# Dash.net
KiCad netlist of a schematic drawn in EAGLE
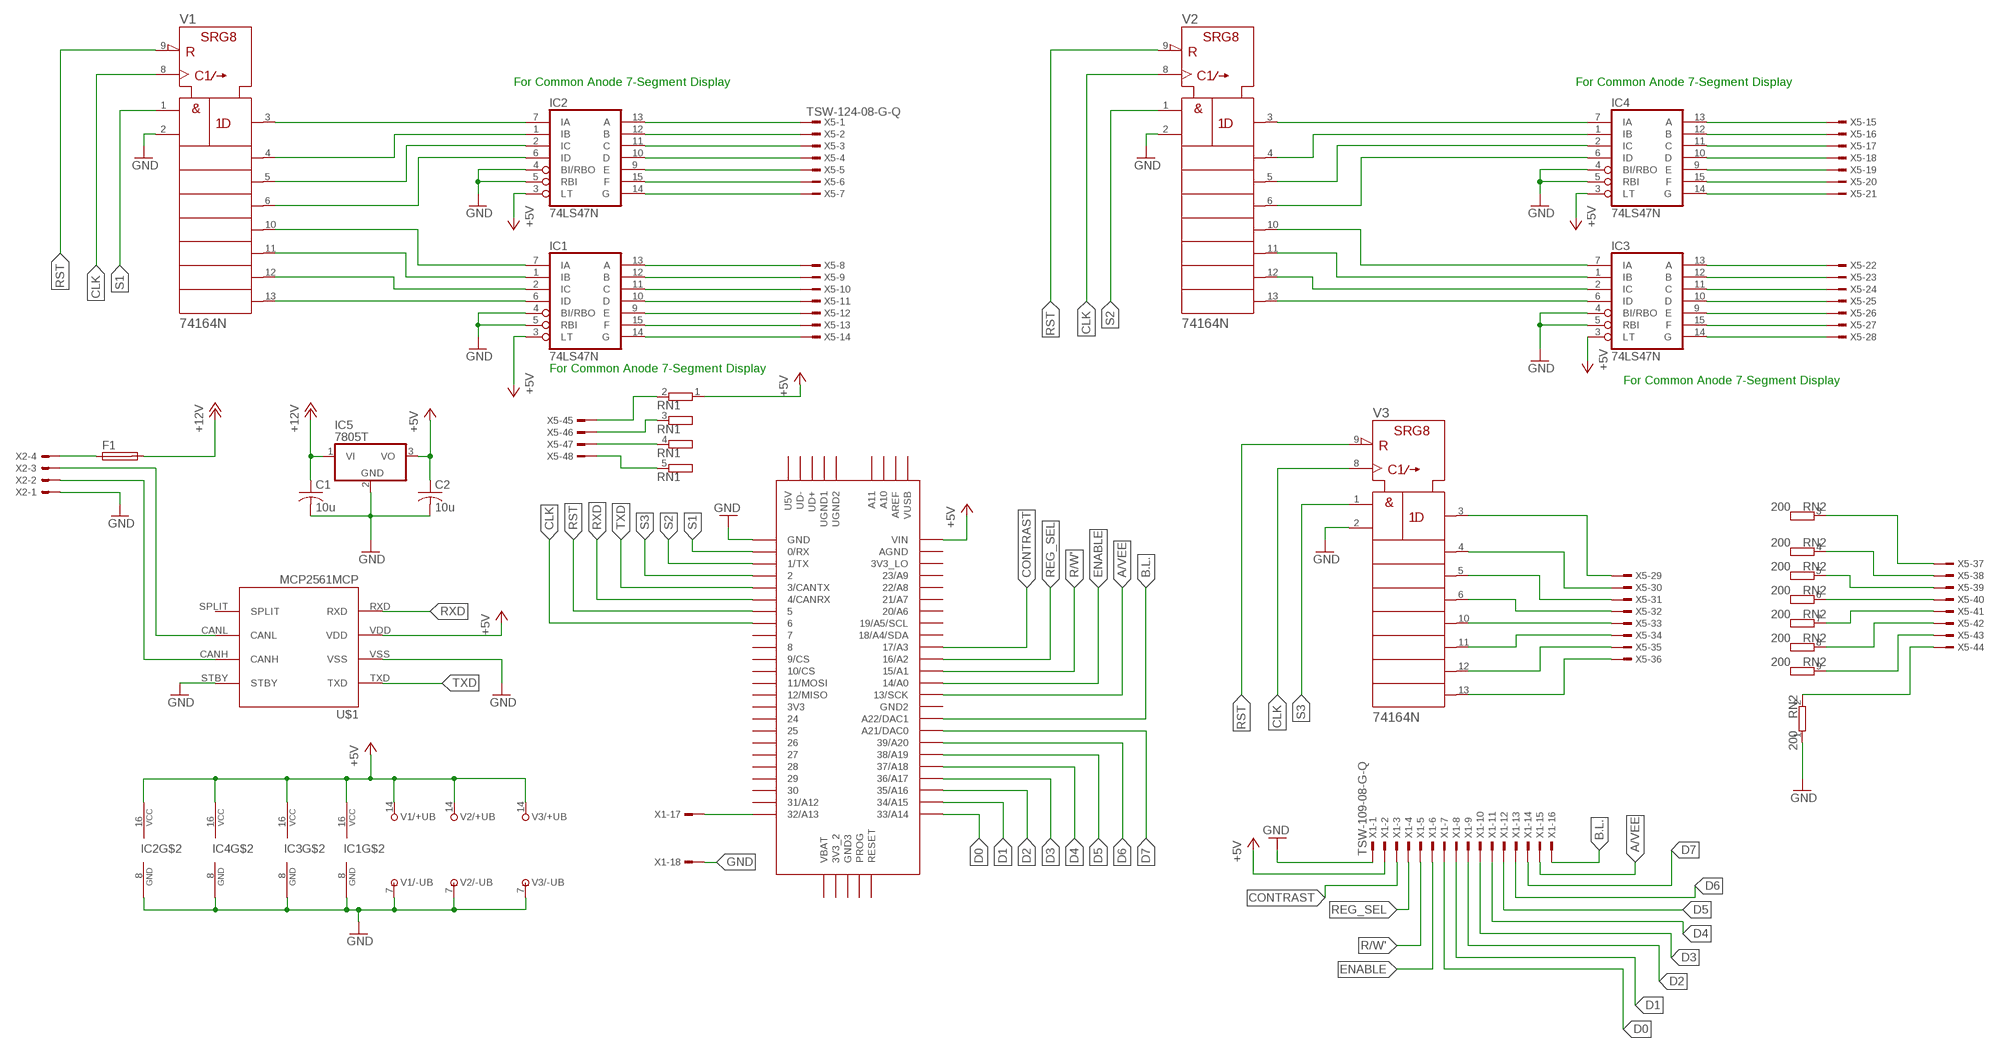
[diagram p0: schematic, sheet 1]

(export (version "E")
  (design (tool "Eeschema 10.0.6"))
  (components
    (comp (ref "C1")
      (value "10u")
      (footprint "eagle-import:C050-024X044")
      (libsource (lib "eagle-import") (part "C-US050-024X044"))
    )
    (comp (ref "C2")
      (value "10u")
      (footprint "eagle-import:C050-024X044")
      (fields (field (name "CAPACITANCE") "10uF"))
      (libsource (lib "eagle-import") (part "C-US050-024X044"))
    )
    (comp (ref "F1")
      (value "FUSEBLANK_5X20MM")
      (footprint "eagle-import:FUSE_HOLDER_5X20MM")
      (libsource (lib "eagle-import") (part "FUSEBLANK_5X20MM"))
    )
    (comp (ref "IC1")
      (value "74LS47N")
      (footprint "eagle-import:DIL16")
      (libsource (lib "eagle-import") (part "7447NLS"))
    )
    (comp (ref "IC2")
      (value "74LS47N")
      (footprint "eagle-import:DIL16")
      (libsource (lib "eagle-import") (part "7447NLS"))
    )
    (comp (ref "IC3")
      (value "74LS47N")
      (footprint "eagle-import:DIL16")
      (libsource (lib "eagle-import") (part "7447NLS"))
    )
    (comp (ref "IC4")
      (value "74LS47N")
      (footprint "eagle-import:DIL16")
      (libsource (lib "eagle-import") (part "7447NLS"))
    )
    (comp (ref "IC5")
      (value "7805T")
      (footprint "eagle-import:TO220H")
      (libsource (lib "eagle-import") (part "78T05"))
    )
    (comp (ref "RN1")
      (value "GE04RP")
      (footprint "eagle-import:SIL5")
      (libsource (lib "eagle-import") (part "GE04RP"))
    )
    (comp (ref "RN2")
      (value "200")
      (footprint "eagle-import:SIL9")
      (libsource (lib "eagle-import") (part "GE08RP"))
    )
    (comp (ref "U$1")
      (value "MCP2561MCP")
      (footprint "eagle-import:MCP2561_PDIP")
      (libsource (lib "eagle-import") (part "MCP2561MCP"))
    )
    (comp (ref "U$2")
      (value "TEENSY_3.5/3.6")
      (footprint "eagle-import:TEENSY_3.5_3.6")
      (libsource (lib "eagle-import") (part "TEENSY_3.5/3.6"))
    )
    (comp (ref "V1")
      (value "74164N")
      (footprint "eagle-import:DIL14")
      (libsource (lib "eagle-import") (part "74164N"))
    )
    (comp (ref "V2")
      (value "74164N")
      (footprint "eagle-import:DIL14")
      (libsource (lib "eagle-import") (part "74164N"))
    )
    (comp (ref "V3")
      (value "74164N")
      (footprint "eagle-import:DIL14")
      (libsource (lib "eagle-import") (part "74164N"))
    )
    (comp (ref "X1")
      (value "TSW-109-08-G-Q")
      (footprint "eagle-import:TSW-109-XX-G-Q")
      (fields (field (name "MF") "Samtec Inc.") (field (name "MPN") "TSW-109-07-G-Q"))
      (libsource (lib "eagle-import") (part "TSW-109--G-Q08"))
    )
    (comp (ref "X2")
      (value "KK-156-4")
      (footprint "eagle-import:KK-156-4")
      (fields (field (name "MF") "MOLEX"))
      (libsource (lib "eagle-import") (part "KK-156-4"))
    )
    (comp (ref "X5")
      (value "TSW-124-08-G-Q")
      (footprint "eagle-import:TSW-124-XX-G-Q")
      (fields (field (name "MF") "Samtec Inc.") (field (name "MPN") "TSW-124-07-G-Q"))
      (libsource (lib "eagle-import") (part "TSW-124--G-Q08"))
    )
  )
  (nets
    (net (code "1") (name "+5V") (class "Default")
      (node (ref "C2") (pin "1") (pinfunction "1_1") (pintype "passive"))
      (node (ref "IC1") (pin "16") (pinfunction "VCC_16") (pintype "power_in"))
      (node (ref "IC1") (pin "3") (pinfunction "LT_3") (pintype "input"))
      (node (ref "IC2") (pin "16") (pinfunction "VCC_16") (pintype "power_in"))
      (node (ref "IC2") (pin "3") (pinfunction "LT_3") (pintype "input"))
      (node (ref "IC3") (pin "16") (pinfunction "VCC_16") (pintype "power_in"))
      (node (ref "IC3") (pin "3") (pinfunction "LT_3") (pintype "input"))
      (node (ref "IC4") (pin "16") (pinfunction "VCC_16") (pintype "power_in"))
      (node (ref "IC4") (pin "3") (pinfunction "LT_3") (pintype "input"))
      (node (ref "IC5") (pin "3") (pinfunction "VO_3") (pintype "passive"))
      (node (ref "RN1") (pin "1") (pinfunction "1_1") (pintype "passive"))
      (node (ref "U$1") (pin "VDD") (pinfunction "VDD_VDD") (pintype "bidirectional"))
      (node (ref "U$2") (pin "VIN") (pinfunction "VIN_VIN") (pintype "bidirectional"))
      (node (ref "V1") (pin "14") (pinfunction "+UB_14") (pintype "power_in"))
      (node (ref "V2") (pin "14") (pinfunction "+UB_14") (pintype "power_in"))
      (node (ref "V3") (pin "14") (pinfunction "+UB_14") (pintype "power_in"))
      (node (ref "X1") (pin "2") (pinfunction "1_2") (pintype "passive"))
    )
    (net (code "2") (name "+12V") (class "Default")
      (node (ref "C1") (pin "1") (pinfunction "1_1") (pintype "passive"))
      (node (ref "F1") (pin "2") (pinfunction "2_2") (pintype "passive"))
      (node (ref "IC5") (pin "1") (pinfunction "VI_1") (pintype "input"))
    )
    (net (code "3") (name "A{slash}VEE") (class "Default")
      (node (ref "U$2") (pin "13/SCK") (pinfunction "13/SCK_13/SCK") (pintype "bidirectional"))
      (node (ref "X1") (pin "15") (pinfunction "1_15") (pintype "passive"))
    )
    (net (code "4") (name "B.L.") (class "Default")
      (node (ref "U$2") (pin "A22/DAC1") (pinfunction "A22/DAC1_A22/DAC1") (pintype "bidirectional"))
      (node (ref "X1") (pin "16") (pinfunction "1_16") (pintype "passive"))
    )
    (net (code "5") (name "CLK") (class "Default")
      (node (ref "U$2") (pin "6") (pinfunction "6_6") (pintype "bidirectional"))
      (node (ref "V1") (pin "8") (pinfunction "CLK_8") (pintype "input"))
      (node (ref "V2") (pin "8") (pinfunction "CLK_8") (pintype "input"))
      (node (ref "V3") (pin "8") (pinfunction "CLK_8") (pintype "input"))
    )
    (net (code "6") (name "CONTRAST") (class "Default")
      (node (ref "U$2") (pin "17/A3") (pinfunction "17/A3_17/A3") (pintype "bidirectional"))
      (node (ref "X1") (pin "3") (pinfunction "1_3") (pintype "passive"))
    )
    (net (code "7") (name "D0") (class "Default")
      (node (ref "U$2") (pin "33/A14") (pinfunction "33/A14_33/A14") (pintype "bidirectional"))
      (node (ref "X1") (pin "7") (pinfunction "1_7") (pintype "passive"))
    )
    (net (code "8") (name "D1") (class "Default")
      (node (ref "IC2") (pin "10") (pinfunction "D_10") (pintype "output"))
      (node (ref "U$2") (pin "34/A15") (pinfunction "34/A15_34/A15") (pintype "bidirectional"))
      (node (ref "X1") (pin "8") (pinfunction "1_8") (pintype "passive"))
      (node (ref "X5") (pin "4") (pinfunction "1_4") (pintype "passive"))
    )
    (net (code "9") (name "D2") (class "Default")
      (node (ref "IC1") (pin "10") (pinfunction "D_10") (pintype "output"))
      (node (ref "U$2") (pin "35/A16") (pinfunction "35/A16_35/A16") (pintype "bidirectional"))
      (node (ref "X1") (pin "9") (pinfunction "1_9") (pintype "passive"))
      (node (ref "X5") (pin "11") (pinfunction "1_11") (pintype "passive"))
    )
    (net (code "10") (name "D3") (class "Default")
      (node (ref "IC3") (pin "10") (pinfunction "D_10") (pintype "output"))
      (node (ref "U$2") (pin "36/A17") (pinfunction "36/A17_36/A17") (pintype "bidirectional"))
      (node (ref "X1") (pin "10") (pinfunction "1_10") (pintype "passive"))
      (node (ref "X5") (pin "25") (pinfunction "1_25") (pintype "passive"))
    )
    (net (code "11") (name "D4") (class "Default")
      (node (ref "IC4") (pin "10") (pinfunction "D_10") (pintype "output"))
      (node (ref "U$2") (pin "37/A18") (pinfunction "37/A18_37/A18") (pintype "bidirectional"))
      (node (ref "X1") (pin "11") (pinfunction "1_11") (pintype "passive"))
      (node (ref "X5") (pin "18") (pinfunction "1_18") (pintype "passive"))
    )
    (net (code "12") (name "D5") (class "Default")
      (node (ref "U$2") (pin "38/A19") (pinfunction "38/A19_38/A19") (pintype "bidirectional"))
      (node (ref "X1") (pin "12") (pinfunction "1_12") (pintype "passive"))
    )
    (net (code "13") (name "D6") (class "Default")
      (node (ref "U$2") (pin "39/A20") (pinfunction "39/A20_39/A20") (pintype "bidirectional"))
      (node (ref "X1") (pin "13") (pinfunction "1_13") (pintype "passive"))
    )
    (net (code "14") (name "D7") (class "Default")
      (node (ref "U$2") (pin "21/DAC0") (pinfunction "A21/DAC0_21/DAC0") (pintype "bidirectional"))
      (node (ref "X1") (pin "14") (pinfunction "1_14") (pintype "passive"))
    )
    (net (code "15") (name "ENABLE") (class "Default")
      (node (ref "U$2") (pin "14/A0") (pinfunction "14/A0_14/A0") (pintype "bidirectional"))
      (node (ref "X1") (pin "6") (pinfunction "1_6") (pintype "passive"))
    )
    (net (code "16") (name "GND") (class "Default")
      (node (ref "C1") (pin "2") (pinfunction "2_2") (pintype "passive"))
      (node (ref "C2") (pin "2") (pinfunction "2_2") (pintype "passive"))
      (node (ref "IC1") (pin "4") (pinfunction "BI/RBO_4") (pintype "input"))
      (node (ref "IC1") (pin "5") (pinfunction "RBI_5") (pintype "input"))
      (node (ref "IC1") (pin "8") (pinfunction "GND_8") (pintype "power_in"))
      (node (ref "IC2") (pin "4") (pinfunction "BI/RBO_4") (pintype "input"))
      (node (ref "IC2") (pin "5") (pinfunction "RBI_5") (pintype "input"))
      (node (ref "IC2") (pin "8") (pinfunction "GND_8") (pintype "power_in"))
      (node (ref "IC3") (pin "4") (pinfunction "BI/RBO_4") (pintype "input"))
      (node (ref "IC3") (pin "5") (pinfunction "RBI_5") (pintype "input"))
      (node (ref "IC3") (pin "8") (pinfunction "GND_8") (pintype "power_in"))
      (node (ref "IC4") (pin "4") (pinfunction "BI/RBO_4") (pintype "input"))
      (node (ref "IC4") (pin "5") (pinfunction "RBI_5") (pintype "input"))
      (node (ref "IC4") (pin "8") (pinfunction "GND_8") (pintype "power_in"))
      (node (ref "IC5") (pin "2") (pinfunction "GND_2") (pintype "passive"))
      (node (ref "RN2") (pin "1") (pinfunction "1_1") (pintype "passive"))
      (node (ref "U$1") (pin "STBY") (pinfunction "STBY_STBY") (pintype "bidirectional"))
      (node (ref "U$1") (pin "VSS") (pinfunction "VSS_VSS") (pintype "bidirectional"))
      (node (ref "U$2") (pin "GND") (pinfunction "GND_GND") (pintype "bidirectional"))
      (node (ref "V1") (pin "2") (pinfunction "B_2") (pintype "input"))
      (node (ref "V1") (pin "7") (pinfunction "-UB_7") (pintype "power_in"))
      (node (ref "V2") (pin "2") (pinfunction "B_2") (pintype "input"))
      (node (ref "V2") (pin "7") (pinfunction "-UB_7") (pintype "power_in"))
      (node (ref "V3") (pin "2") (pinfunction "B_2") (pintype "input"))
      (node (ref "V3") (pin "7") (pinfunction "-UB_7") (pintype "power_in"))
      (node (ref "X1") (pin "1") (pinfunction "1_1") (pintype "passive"))
      (node (ref "X1") (pin "18") (pinfunction "1_18") (pintype "passive"))
      (node (ref "X2") (pin "1") (pinfunction "S_1") (pintype "passive"))
    )
    (net (code "17") (name "Net-(IC1A-A)") (class "Default")
      (node (ref "IC1") (pin "13") (pinfunction "A_13") (pintype "output"))
      (node (ref "X5") (pin "8") (pinfunction "1_8") (pintype "passive"))
    )
    (net (code "18") (name "Net-(IC1A-B)") (class "Default")
      (node (ref "IC1") (pin "12") (pinfunction "B_12") (pintype "output"))
      (node (ref "X5") (pin "9") (pinfunction "1_9") (pintype "passive"))
    )
    (net (code "19") (name "Net-(IC1A-C)") (class "Default")
      (node (ref "IC1") (pin "11") (pinfunction "C_11") (pintype "output"))
      (node (ref "X5") (pin "10") (pinfunction "1_10") (pintype "passive"))
    )
    (net (code "20") (name "Net-(IC1A-E)") (class "Default")
      (node (ref "IC1") (pin "9") (pinfunction "E_9") (pintype "output"))
      (node (ref "X5") (pin "12") (pinfunction "1_12") (pintype "passive"))
    )
    (net (code "21") (name "Net-(IC1A-F)") (class "Default")
      (node (ref "IC1") (pin "15") (pinfunction "F_15") (pintype "output"))
      (node (ref "X5") (pin "13") (pinfunction "1_13") (pintype "passive"))
    )
    (net (code "22") (name "Net-(IC1A-G)") (class "Default")
      (node (ref "IC1") (pin "14") (pinfunction "G_14") (pintype "output"))
      (node (ref "X5") (pin "14") (pinfunction "1_14") (pintype "passive"))
    )
    (net (code "23") (name "Net-(IC1A-IA)") (class "Default")
      (node (ref "IC1") (pin "7") (pinfunction "IA_7") (pintype "input"))
      (node (ref "V1") (pin "10") (pinfunction "QE_10") (pintype "output"))
    )
    (net (code "24") (name "Net-(IC1A-IB)") (class "Default")
      (node (ref "IC1") (pin "1") (pinfunction "IB_1") (pintype "input"))
      (node (ref "V1") (pin "11") (pinfunction "QF_11") (pintype "output"))
    )
    (net (code "25") (name "Net-(IC1A-IC)") (class "Default")
      (node (ref "IC1") (pin "2") (pinfunction "IC_2") (pintype "input"))
      (node (ref "V1") (pin "12") (pinfunction "QG_12") (pintype "output"))
    )
    (net (code "26") (name "Net-(IC1A-ID)") (class "Default")
      (node (ref "IC1") (pin "6") (pinfunction "ID_6") (pintype "input"))
      (node (ref "V1") (pin "13") (pinfunction "QH_13") (pintype "output"))
    )
    (net (code "27") (name "Net-(IC2A-A)") (class "Default")
      (node (ref "IC2") (pin "13") (pinfunction "A_13") (pintype "output"))
      (node (ref "X5") (pin "1") (pinfunction "1_1") (pintype "passive"))
    )
    (net (code "28") (name "Net-(IC2A-B)") (class "Default")
      (node (ref "IC2") (pin "12") (pinfunction "B_12") (pintype "output"))
      (node (ref "X5") (pin "2") (pinfunction "1_2") (pintype "passive"))
    )
    (net (code "29") (name "Net-(IC2A-C)") (class "Default")
      (node (ref "IC2") (pin "11") (pinfunction "C_11") (pintype "output"))
      (node (ref "X5") (pin "3") (pinfunction "1_3") (pintype "passive"))
    )
    (net (code "30") (name "Net-(IC2A-E)") (class "Default")
      (node (ref "IC2") (pin "9") (pinfunction "E_9") (pintype "output"))
      (node (ref "X5") (pin "5") (pinfunction "1_5") (pintype "passive"))
    )
    (net (code "31") (name "Net-(IC2A-F)") (class "Default")
      (node (ref "IC2") (pin "15") (pinfunction "F_15") (pintype "output"))
      (node (ref "X5") (pin "6") (pinfunction "1_6") (pintype "passive"))
    )
    (net (code "32") (name "Net-(IC2A-G)") (class "Default")
      (node (ref "IC2") (pin "14") (pinfunction "G_14") (pintype "output"))
      (node (ref "X5") (pin "7") (pinfunction "1_7") (pintype "passive"))
    )
    (net (code "33") (name "Net-(IC2A-IA)") (class "Default")
      (node (ref "IC2") (pin "7") (pinfunction "IA_7") (pintype "input"))
      (node (ref "V1") (pin "3") (pinfunction "QA_3") (pintype "output"))
    )
    (net (code "34") (name "Net-(IC2A-IB)") (class "Default")
      (node (ref "IC2") (pin "1") (pinfunction "IB_1") (pintype "input"))
      (node (ref "V1") (pin "4") (pinfunction "QB_4") (pintype "output"))
    )
    (net (code "35") (name "Net-(IC2A-IC)") (class "Default")
      (node (ref "IC2") (pin "2") (pinfunction "IC_2") (pintype "input"))
      (node (ref "V1") (pin "5") (pinfunction "QC_5") (pintype "output"))
    )
    (net (code "36") (name "Net-(IC2A-ID)") (class "Default")
      (node (ref "IC2") (pin "6") (pinfunction "ID_6") (pintype "input"))
      (node (ref "V1") (pin "6") (pinfunction "QD_6") (pintype "output"))
    )
    (net (code "37") (name "Net-(IC3A-A)") (class "Default")
      (node (ref "IC3") (pin "13") (pinfunction "A_13") (pintype "output"))
      (node (ref "X5") (pin "22") (pinfunction "1_22") (pintype "passive"))
    )
    (net (code "38") (name "Net-(IC3A-B)") (class "Default")
      (node (ref "IC3") (pin "12") (pinfunction "B_12") (pintype "output"))
      (node (ref "X5") (pin "23") (pinfunction "1_23") (pintype "passive"))
    )
    (net (code "39") (name "Net-(IC3A-C)") (class "Default")
      (node (ref "IC3") (pin "11") (pinfunction "C_11") (pintype "output"))
      (node (ref "X5") (pin "24") (pinfunction "1_24") (pintype "passive"))
    )
    (net (code "40") (name "Net-(IC3A-E)") (class "Default")
      (node (ref "IC3") (pin "9") (pinfunction "E_9") (pintype "output"))
      (node (ref "X5") (pin "26") (pinfunction "1_26") (pintype "passive"))
    )
    (net (code "41") (name "Net-(IC3A-F)") (class "Default")
      (node (ref "IC3") (pin "15") (pinfunction "F_15") (pintype "output"))
      (node (ref "X5") (pin "27") (pinfunction "1_27") (pintype "passive"))
    )
    (net (code "42") (name "Net-(IC3A-G)") (class "Default")
      (node (ref "IC3") (pin "14") (pinfunction "G_14") (pintype "output"))
      (node (ref "X5") (pin "28") (pinfunction "1_28") (pintype "passive"))
    )
    (net (code "43") (name "Net-(IC3A-IA)") (class "Default")
      (node (ref "IC3") (pin "7") (pinfunction "IA_7") (pintype "input"))
      (node (ref "V2") (pin "10") (pinfunction "QE_10") (pintype "output"))
    )
    (net (code "44") (name "Net-(IC3A-IB)") (class "Default")
      (node (ref "IC3") (pin "1") (pinfunction "IB_1") (pintype "input"))
      (node (ref "V2") (pin "11") (pinfunction "QF_11") (pintype "output"))
    )
    (net (code "45") (name "Net-(IC3A-IC)") (class "Default")
      (node (ref "IC3") (pin "2") (pinfunction "IC_2") (pintype "input"))
      (node (ref "V2") (pin "12") (pinfunction "QG_12") (pintype "output"))
    )
    (net (code "46") (name "Net-(IC3A-ID)") (class "Default")
      (node (ref "IC3") (pin "6") (pinfunction "ID_6") (pintype "input"))
      (node (ref "V2") (pin "13") (pinfunction "QH_13") (pintype "output"))
    )
    (net (code "47") (name "Net-(IC4A-A)") (class "Default")
      (node (ref "IC4") (pin "13") (pinfunction "A_13") (pintype "output"))
      (node (ref "X5") (pin "15") (pinfunction "1_15") (pintype "passive"))
    )
    (net (code "48") (name "Net-(IC4A-B)") (class "Default")
      (node (ref "IC4") (pin "12") (pinfunction "B_12") (pintype "output"))
      (node (ref "X5") (pin "16") (pinfunction "1_16") (pintype "passive"))
    )
    (net (code "49") (name "Net-(IC4A-C)") (class "Default")
      (node (ref "IC4") (pin "11") (pinfunction "C_11") (pintype "output"))
      (node (ref "X5") (pin "17") (pinfunction "1_17") (pintype "passive"))
    )
    (net (code "50") (name "Net-(IC4A-E)") (class "Default")
      (node (ref "IC4") (pin "9") (pinfunction "E_9") (pintype "output"))
      (node (ref "X5") (pin "19") (pinfunction "1_19") (pintype "passive"))
    )
    (net (code "51") (name "Net-(IC4A-F)") (class "Default")
      (node (ref "IC4") (pin "15") (pinfunction "F_15") (pintype "output"))
      (node (ref "X5") (pin "20") (pinfunction "1_20") (pintype "passive"))
    )
    (net (code "52") (name "Net-(IC4A-G)") (class "Default")
      (node (ref "IC4") (pin "14") (pinfunction "G_14") (pintype "output"))
      (node (ref "X5") (pin "21") (pinfunction "1_21") (pintype "passive"))
    )
    (net (code "53") (name "Net-(IC4A-IA)") (class "Default")
      (node (ref "IC4") (pin "7") (pinfunction "IA_7") (pintype "input"))
      (node (ref "V2") (pin "3") (pinfunction "QA_3") (pintype "output"))
    )
    (net (code "54") (name "Net-(IC4A-IB)") (class "Default")
      (node (ref "IC4") (pin "1") (pinfunction "IB_1") (pintype "input"))
      (node (ref "V2") (pin "4") (pinfunction "QB_4") (pintype "output"))
    )
    (net (code "55") (name "Net-(IC4A-IC)") (class "Default")
      (node (ref "IC4") (pin "2") (pinfunction "IC_2") (pintype "input"))
      (node (ref "V2") (pin "5") (pinfunction "QC_5") (pintype "output"))
    )
    (net (code "56") (name "Net-(IC4A-ID)") (class "Default")
      (node (ref "IC4") (pin "6") (pinfunction "ID_6") (pintype "input"))
      (node (ref "V2") (pin "6") (pinfunction "QD_6") (pintype "output"))
    )
    (net (code "57") (name "Net-(RN1B-2)") (class "Default")
      (node (ref "RN1") (pin "3") (pinfunction "2_3") (pintype "passive"))
      (node (ref "X5") (pin "46") (pinfunction "1_46") (pintype "passive"))
    )
    (net (code "58") (name "Net-(RN1C-2)") (class "Default")
      (node (ref "RN1") (pin "4") (pinfunction "2_4") (pintype "passive"))
      (node (ref "X5") (pin "47") (pinfunction "1_47") (pintype "passive"))
    )
    (net (code "59") (name "Net-(RN1D-2)") (class "Default")
      (node (ref "RN1") (pin "5") (pinfunction "2_5") (pintype "passive"))
      (node (ref "X5") (pin "48") (pinfunction "1_48") (pintype "passive"))
    )
    (net (code "60") (name "Net-(RN2B-2)") (class "Default")
      (node (ref "RN2") (pin "3") (pinfunction "2_3") (pintype "passive"))
      (node (ref "X5") (pin "37") (pinfunction "1_37") (pintype "passive"))
    )
    (net (code "61") (name "Net-(RN2C-2)") (class "Default")
      (node (ref "RN2") (pin "4") (pinfunction "2_4") (pintype "passive"))
      (node (ref "X5") (pin "38") (pinfunction "1_38") (pintype "passive"))
    )
    (net (code "62") (name "Net-(RN2D-2)") (class "Default")
      (node (ref "RN2") (pin "5") (pinfunction "2_5") (pintype "passive"))
      (node (ref "X5") (pin "39") (pinfunction "1_39") (pintype "passive"))
    )
    (net (code "63") (name "Net-(RN2E-2)") (class "Default")
      (node (ref "RN2") (pin "6") (pinfunction "2_6") (pintype "passive"))
      (node (ref "X5") (pin "40") (pinfunction "1_40") (pintype "passive"))
    )
    (net (code "64") (name "Net-(RN2F-2)") (class "Default")
      (node (ref "RN2") (pin "7") (pinfunction "2_7") (pintype "passive"))
      (node (ref "X5") (pin "41") (pinfunction "1_41") (pintype "passive"))
    )
    (net (code "65") (name "Net-(RN2G-2)") (class "Default")
      (node (ref "RN2") (pin "8") (pinfunction "2_8") (pintype "passive"))
      (node (ref "X5") (pin "42") (pinfunction "1_42") (pintype "passive"))
    )
    (net (code "66") (name "Net-(RN2H-2)") (class "Default")
      (node (ref "RN2") (pin "9") (pinfunction "2_9") (pintype "passive"))
      (node (ref "X5") (pin "43") (pinfunction "1_43") (pintype "passive"))
    )
    (net (code "67") (name "Net-(V3C-QA)") (class "Default")
      (node (ref "V3") (pin "3") (pinfunction "QA_3") (pintype "output"))
      (node (ref "X5") (pin "29") (pinfunction "1_29") (pintype "passive"))
    )
    (net (code "68") (name "Net-(V3C-QB)") (class "Default")
      (node (ref "V3") (pin "4") (pinfunction "QB_4") (pintype "output"))
      (node (ref "X5") (pin "30") (pinfunction "1_30") (pintype "passive"))
    )
    (net (code "69") (name "Net-(V3C-QC)") (class "Default")
      (node (ref "V3") (pin "5") (pinfunction "QC_5") (pintype "output"))
      (node (ref "X5") (pin "31") (pinfunction "1_31") (pintype "passive"))
    )
    (net (code "70") (name "Net-(V3C-QD)") (class "Default")
      (node (ref "V3") (pin "6") (pinfunction "QD_6") (pintype "output"))
      (node (ref "X5") (pin "32") (pinfunction "1_32") (pintype "passive"))
    )
    (net (code "71") (name "Net-(V3C-QE)") (class "Default")
      (node (ref "V3") (pin "10") (pinfunction "QE_10") (pintype "output"))
      (node (ref "X5") (pin "33") (pinfunction "1_33") (pintype "passive"))
    )
    (net (code "72") (name "Net-(V3C-QF)") (class "Default")
      (node (ref "V3") (pin "11") (pinfunction "QF_11") (pintype "output"))
      (node (ref "X5") (pin "34") (pinfunction "1_34") (pintype "passive"))
    )
    (net (code "73") (name "Net-(V3C-QG)") (class "Default")
      (node (ref "V3") (pin "12") (pinfunction "QG_12") (pintype "output"))
      (node (ref "X5") (pin "35") (pinfunction "1_35") (pintype "passive"))
    )
    (net (code "74") (name "Net-(V3C-QH)") (class "Default")
      (node (ref "V3") (pin "13") (pinfunction "QH_13") (pintype "output"))
      (node (ref "X5") (pin "36") (pinfunction "1_36") (pintype "passive"))
    )
    (net (code "75") (name "Net-(X1I-1)") (class "Default")
      (node (ref "U$2") (pin "32/A13") (pinfunction "32/A13_32/A13") (pintype "bidirectional"))
      (node (ref "X1") (pin "17") (pinfunction "1_17") (pintype "passive"))
    )
    (net (code "76") (name "Net-(X2B-S)") (class "Default")
      (node (ref "U$1") (pin "CANH") (pinfunction "CANH_CANH") (pintype "bidirectional"))
      (node (ref "X2") (pin "2") (pinfunction "S_2") (pintype "passive"))
    )
    (net (code "77") (name "Net-(X2C-S)") (class "Default")
      (node (ref "U$1") (pin "CANL") (pinfunction "CANL_CANL") (pintype "bidirectional"))
      (node (ref "X2") (pin "3") (pinfunction "S_3") (pintype "passive"))
    )
    (net (code "78") (name "Net-(X2D-S)") (class "Default")
      (node (ref "F1") (pin "1") (pinfunction "1_1") (pintype "passive"))
      (node (ref "X2") (pin "4") (pinfunction "S_4") (pintype "passive"))
    )
    (net (code "79") (name "Net-(X5AM-1)") (class "Default")
      (node (ref "RN2") (pin "2") (pinfunction "2_2") (pintype "passive"))
      (node (ref "X5") (pin "44") (pinfunction "1_44") (pintype "passive"))
    )
    (net (code "80") (name "Net-(X5AN-1)") (class "Default")
      (node (ref "RN1") (pin "2") (pinfunction "2_2") (pintype "passive"))
      (node (ref "X5") (pin "45") (pinfunction "1_45") (pintype "passive"))
    )
    (net (code "81") (name "REG_SEL") (class "Default")
      (node (ref "U$2") (pin "16/A2") (pinfunction "16/A2_16/A2") (pintype "bidirectional"))
      (node (ref "X1") (pin "4") (pinfunction "1_4") (pintype "passive"))
    )
    (net (code "82") (name "RST") (class "Default")
      (node (ref "U$2") (pin "5") (pinfunction "5_5") (pintype "bidirectional"))
      (node (ref "V1") (pin "9") (pinfunction "~{CLR}_9") (pintype "input"))
      (node (ref "V2") (pin "9") (pinfunction "~{CLR}_9") (pintype "input"))
      (node (ref "V3") (pin "9") (pinfunction "~{CLR}_9") (pintype "input"))
    )
    (net (code "83") (name "RXD") (class "Default")
      (node (ref "U$1") (pin "RXD") (pinfunction "RXD_RXD") (pintype "bidirectional"))
      (node (ref "U$2") (pin "4/CANRX") (pinfunction "4/CANRX_4/CANRX") (pintype "bidirectional"))
    )
    (net (code "84") (name "R{slash}W'") (class "Default")
      (node (ref "U$2") (pin "15/A1") (pinfunction "15/A1_15/A1") (pintype "bidirectional"))
      (node (ref "X1") (pin "5") (pinfunction "1_5") (pintype "passive"))
    )
    (net (code "85") (name "S1") (class "Default")
      (node (ref "U$2") (pin "0/RX") (pinfunction "0/RX_0/RX") (pintype "bidirectional"))
      (node (ref "V1") (pin "1") (pinfunction "A_1") (pintype "input"))
    )
    (net (code "86") (name "S2") (class "Default")
      (node (ref "U$2") (pin "1/TX") (pinfunction "1/TX_1/TX") (pintype "bidirectional"))
      (node (ref "V2") (pin "1") (pinfunction "A_1") (pintype "input"))
    )
    (net (code "87") (name "S3") (class "Default")
      (node (ref "U$2") (pin "2") (pinfunction "2_2") (pintype "bidirectional"))
      (node (ref "V3") (pin "1") (pinfunction "A_1") (pintype "input"))
    )
    (net (code "88") (name "TXD") (class "Default")
      (node (ref "U$1") (pin "TXD") (pinfunction "TXD_TXD") (pintype "bidirectional"))
      (node (ref "U$2") (pin "3/CANTX") (pinfunction "3/CANTX_3/CANTX") (pintype "bidirectional"))
    )
    (net (code "89") (name "unconnected-(U$1-PadSPLIT)") (class "Default")
      (node (ref "U$1") (pin "SPLIT") (pinfunction "SPLIT_SPLIT") (pintype "bidirectional"))
    )
    (net (code "90") (name "unconnected-(U$2-Pad3V3)") (class "Default")
      (node (ref "U$2") (pin "3V3") (pinfunction "3V3_3V3") (pintype "bidirectional"))
    )
    (net (code "91") (name "unconnected-(U$2-Pad3V3_2)") (class "Default")
      (node (ref "U$2") (pin "3V3_2") (pinfunction "3V3_2_3V3_2") (pintype "bidirectional"))
    )
    (net (code "92") (name "unconnected-(U$2-Pad3V3_LO)") (class "Default")
      (node (ref "U$2") (pin "3V3_LO") (pinfunction "3V3_LO_3V3_LO") (pintype "bidirectional"))
    )
    (net (code "93") (name "unconnected-(U$2-Pad7)") (class "Default")
      (node (ref "U$2") (pin "7") (pinfunction "7_7") (pintype "bidirectional"))
    )
    (net (code "94") (name "unconnected-(U$2-Pad8)") (class "Default")
      (node (ref "U$2") (pin "8") (pinfunction "8_8") (pintype "bidirectional"))
    )
    (net (code "95") (name "unconnected-(U$2-Pad9{slash}CS)") (class "Default")
      (node (ref "U$2") (pin "9/CS") (pinfunction "9/CS_9/CS") (pintype "bidirectional"))
    )
    (net (code "96") (name "unconnected-(U$2-Pad10{slash}CS)") (class "Default")
      (node (ref "U$2") (pin "10/CS") (pinfunction "10/CS_10/CS") (pintype "bidirectional"))
    )
    (net (code "97") (name "unconnected-(U$2-Pad11{slash}MOSI)") (class "Default")
      (node (ref "U$2") (pin "11/MOSI") (pinfunction "11/MOSI_11/MOSI") (pintype "bidirectional"))
    )
    (net (code "98") (name "unconnected-(U$2-Pad12{slash}MISO)") (class "Default")
      (node (ref "U$2") (pin "12/MISO") (pinfunction "12/MISO_12/MISO") (pintype "bidirectional"))
    )
    (net (code "99") (name "unconnected-(U$2-Pad18{slash}A4{slash}SDA)") (class "Default")
      (node (ref "U$2") (pin "18/A4/SDA") (pinfunction "18/A4/SDA_18/A4/SDA") (pintype "bidirectional"))
    )
    (net (code "100") (name "unconnected-(U$2-Pad19{slash}A5{slash}SCL)") (class "Default")
      (node (ref "U$2") (pin "19/A5/SCL") (pinfunction "19/A5/SCL_19/A5/SCL") (pintype "bidirectional"))
    )
    (net (code "101") (name "unconnected-(U$2-Pad20{slash}A6)") (class "Default")
      (node (ref "U$2") (pin "20/A6") (pinfunction "20/A6_20/A6") (pintype "bidirectional"))
    )
    (net (code "102") (name "unconnected-(U$2-Pad21{slash}A7)") (class "Default")
      (node (ref "U$2") (pin "21/A7") (pinfunction "21/A7_21/A7") (pintype "bidirectional"))
    )
    (net (code "103") (name "unconnected-(U$2-Pad22{slash}A8)") (class "Default")
      (node (ref "U$2") (pin "22/A8") (pinfunction "22/A8_22/A8") (pintype "bidirectional"))
    )
    (net (code "104") (name "unconnected-(U$2-Pad23{slash}A9)") (class "Default")
      (node (ref "U$2") (pin "23/A9") (pinfunction "23/A9_23/A9") (pintype "bidirectional"))
    )
    (net (code "105") (name "unconnected-(U$2-Pad24)") (class "Default")
      (node (ref "U$2") (pin "24") (pinfunction "24_24") (pintype "bidirectional"))
    )
    (net (code "106") (name "unconnected-(U$2-Pad25)") (class "Default")
      (node (ref "U$2") (pin "25") (pinfunction "25_25") (pintype "bidirectional"))
    )
    (net (code "107") (name "unconnected-(U$2-Pad26)") (class "Default")
      (node (ref "U$2") (pin "26") (pinfunction "26_26") (pintype "bidirectional"))
    )
    (net (code "108") (name "unconnected-(U$2-Pad27)") (class "Default")
      (node (ref "U$2") (pin "27") (pinfunction "27_27") (pintype "bidirectional"))
    )
    (net (code "109") (name "unconnected-(U$2-Pad28)") (class "Default")
      (node (ref "U$2") (pin "28") (pinfunction "28_28") (pintype "bidirectional"))
    )
    (net (code "110") (name "unconnected-(U$2-Pad29)") (class "Default")
      (node (ref "U$2") (pin "29") (pinfunction "29_29") (pintype "bidirectional"))
    )
    (net (code "111") (name "unconnected-(U$2-Pad30)") (class "Default")
      (node (ref "U$2") (pin "30") (pinfunction "30_30") (pintype "bidirectional"))
    )
    (net (code "112") (name "unconnected-(U$2-Pad31{slash}A12)") (class "Default")
      (node (ref "U$2") (pin "31/A12") (pinfunction "31/A12_31/A12") (pintype "bidirectional"))
    )
    (net (code "113") (name "unconnected-(U$2-PadA10)") (class "Default")
      (node (ref "U$2") (pin "A10") (pinfunction "A10_A10") (pintype "bidirectional"))
    )
    (net (code "114") (name "unconnected-(U$2-PadA11)") (class "Default")
      (node (ref "U$2") (pin "A11") (pinfunction "A11_A11") (pintype "bidirectional"))
    )
    (net (code "115") (name "unconnected-(U$2-PadAGND)") (class "Default")
      (node (ref "U$2") (pin "AGND") (pinfunction "AGND_AGND") (pintype "bidirectional"))
    )
    (net (code "116") (name "unconnected-(U$2-PadAREF)") (class "Default")
      (node (ref "U$2") (pin "AREF") (pinfunction "AREF_AREF") (pintype "bidirectional"))
    )
    (net (code "117") (name "unconnected-(U$2-PadGND2)") (class "Default")
      (node (ref "U$2") (pin "GND2") (pinfunction "GND2_GND2") (pintype "bidirectional"))
    )
    (net (code "118") (name "unconnected-(U$2-PadGND3)") (class "Default")
      (node (ref "U$2") (pin "GND3") (pinfunction "GND3_GND3") (pintype "bidirectional"))
    )
    (net (code "119") (name "unconnected-(U$2-PadPROG)") (class "Default")
      (node (ref "U$2") (pin "PROG") (pinfunction "PROG_PROG") (pintype "bidirectional"))
    )
    (net (code "120") (name "unconnected-(U$2-PadRESET)") (class "Default")
      (node (ref "U$2") (pin "RESET") (pinfunction "RESET_RESET") (pintype "bidirectional"))
    )
    (net (code "121") (name "unconnected-(U$2-PadU5V)") (class "Default")
      (node (ref "U$2") (pin "U5V") (pinfunction "U5V_U5V") (pintype "bidirectional"))
    )
    (net (code "122") (name "unconnected-(U$2-PadUD+)") (class "Default")
      (node (ref "U$2") (pin "UD+") (pinfunction "UD+_UD+") (pintype "bidirectional"))
    )
    (net (code "123") (name "unconnected-(U$2-PadUD-)") (class "Default")
      (node (ref "U$2") (pin "UD-") (pinfunction "UD-_UD-") (pintype "bidirectional"))
    )
    (net (code "124") (name "unconnected-(U$2-PadUGND1)") (class "Default")
      (node (ref "U$2") (pin "UGND1") (pinfunction "UGND1_UGND1") (pintype "bidirectional"))
    )
    (net (code "125") (name "unconnected-(U$2-PadUGND2)") (class "Default")
      (node (ref "U$2") (pin "UGND2") (pinfunction "UGND2_UGND2") (pintype "bidirectional"))
    )
    (net (code "126") (name "unconnected-(U$2-PadVBAT)") (class "Default")
      (node (ref "U$2") (pin "VBAT") (pinfunction "VBAT_VBAT") (pintype "bidirectional"))
    )
    (net (code "127") (name "unconnected-(U$2-PadVUSB)") (class "Default")
      (node (ref "U$2") (pin "VUSB") (pinfunction "VUSB_VUSB") (pintype "bidirectional"))
    )
  )
)
